# watter_flow_metter_2.net
KiCad netlist of a schematic drawn in EAGLE
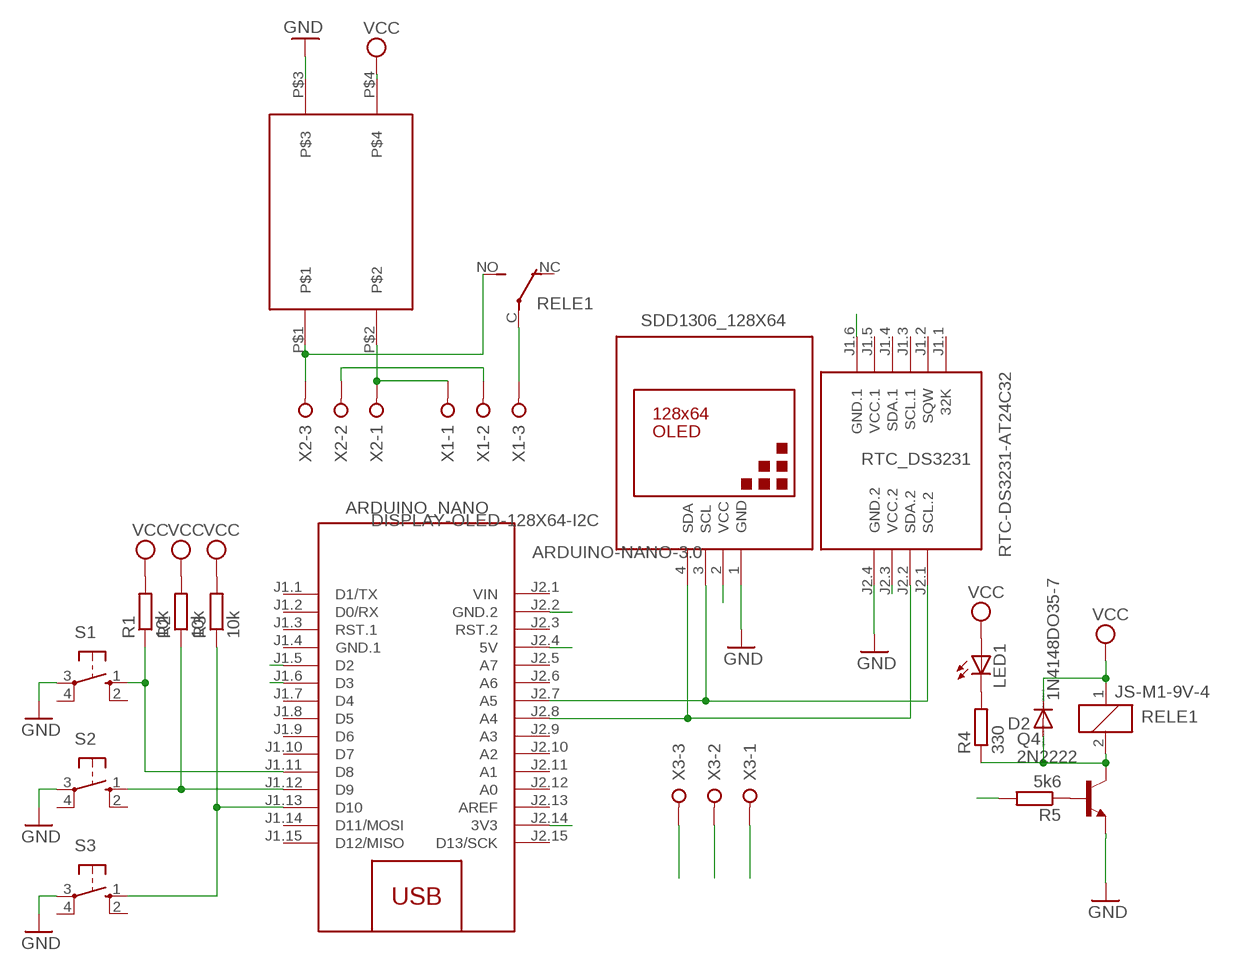
[diagram p0: schematic, sheet 1]

(export (version "E")
  (design (tool "Eeschema 10.0.6"))
  (components
    (comp (ref "ARDUINO_NANO")
      (value "ARDUINO-NANO-3.0")
      (footprint "eagle-import:ARDUINO-NANO-3.0")
      (libsource (lib "eagle-import") (part "ARDUINO-NANO-3.0"))
    )
    (comp (ref "D2")
      (value "1N4148DO35-7")
      (footprint "eagle-import:DO35-7")
      (libsource (lib "eagle-import") (part "1N4148DO35-7"))
    )
    (comp (ref "LED1")
      (value "LED3MM")
      (footprint "eagle-import:LED3MM")
      (libsource (lib "eagle-import") (part "LED3MM"))
    )
    (comp (ref "Q4")
      (value "2N2222")
      (footprint "eagle-import:TO92")
      (libsource (lib "eagle-import") (part "2N5088"))
    )
    (comp (ref "R1")
      (value "10k")
      (footprint "eagle-import:0207_10")
      (libsource (lib "eagle-import") (part "R-EU_0207/10"))
    )
    (comp (ref "R2")
      (value "10k")
      (footprint "eagle-import:0207_10")
      (libsource (lib "eagle-import") (part "R-EU_0207/10"))
    )
    (comp (ref "R3")
      (value "10k")
      (footprint "eagle-import:0207_10")
      (libsource (lib "eagle-import") (part "R-EU_0207/10"))
    )
    (comp (ref "R4")
      (value "330")
      (footprint "eagle-import:0207_10")
      (libsource (lib "eagle-import") (part "R-EU_0207/10"))
    )
    (comp (ref "R5")
      (value "5k6")
      (footprint "eagle-import:0207_10")
      (libsource (lib "eagle-import") (part "R-EU_0207/10"))
    )
    (comp (ref "RELE1")
      (value "JS-M1-9V-4")
      (footprint "eagle-import:JS-M")
      (libsource (lib "eagle-import") (part "JS-M1-9V-4"))
    )
    (comp (ref "RTC_DS3231")
      (value "RTC-DS3231-AT24C32")
      (footprint "eagle-import:RTC-DS3231-AT24C32")
      (libsource (lib "eagle-import") (part "RTC-DS3231-AT24C32"))
    )
    (comp (ref "S1")
      (value "10-XX")
      (footprint "eagle-import:B3F-10XX")
      (fields (field (name "MPN") "B3F-1000"))
      (libsource (lib "eagle-import") (part "10-XX"))
    )
    (comp (ref "S2")
      (value "10-XX")
      (footprint "eagle-import:B3F-10XX")
      (fields (field (name "MPN") "B3F-1000"))
      (libsource (lib "eagle-import") (part "10-XX"))
    )
    (comp (ref "S3")
      (value "10-XX")
      (footprint "eagle-import:B3F-10XX")
      (fields (field (name "MPN") "B3F-1000"))
      (libsource (lib "eagle-import") (part "10-XX"))
    )
    (comp (ref "SDD1306_128X64")
      (value "DISPLAY-OLED-128X64-I2C")
      (footprint "eagle-import:DISPLAY-OLED-128X64-I2C")
      (libsource (lib "eagle-import") (part "DISPLAY-OLED-128X64-I2C"))
    )
    (comp (ref "U$6")
      (value "HLK-PM01")
      (footprint "eagle-import:HLK-PM01")
      (libsource (lib "eagle-import") (part "HLK-PM01"))
    )
    (comp (ref "X1")
      (value "W237-3E")
      (footprint "eagle-import:W237-3E")
      (libsource (lib "eagle-import") (part "W237-3E"))
    )
    (comp (ref "X2")
      (value "W237-3E")
      (footprint "eagle-import:W237-3E")
      (libsource (lib "eagle-import") (part "W237-3E"))
    )
    (comp (ref "X3")
      (value "W237-3E")
      (footprint "eagle-import:W237-3E")
      (libsource (lib "eagle-import") (part "W237-3E"))
    )
  )
  (nets
    (net (code "1") (name "/3.3V") (class "Default")
      (node (ref "ARDUINO_NANO") (pin "J2.14") (pinfunction "3V3_J2.14") (pintype "power_in"))
      (node (ref "RTC_DS3231") (pin "J2.3") (pinfunction "VCC.2_J2.3") (pintype "power_in"))
      (node (ref "SDD1306_128X64") (pin "2") (pinfunction "VCC_2") (pintype "power_in"))
    )
    (net (code "2") (name "/D2") (class "Default")
      (node (ref "ARDUINO_NANO") (pin "J1.5") (pinfunction "D2_J1.5") (pintype "bidirectional"))
      (node (ref "X3") (pin "2") (pinfunction "KL_2") (pintype "passive"))
    )
    (net (code "3") (name "/D3") (class "Default")
      (node (ref "ARDUINO_NANO") (pin "J1.6") (pinfunction "D3_J1.6") (pintype "bidirectional"))
      (node (ref "R5") (pin "2") (pinfunction "2_2") (pintype "passive"))
    )
    (net (code "4") (name "/GND.1") (class "Default")
      (node (ref "ARDUINO_NANO") (pin "J1.4") (pinfunction "GND.1_J1.4") (pintype "power_in"))
    )
    (net (code "5") (name "/VCC.1") (class "Default")
      (node (ref "RTC_DS3231") (pin "J1.5") (pinfunction "VCC.1_J1.5") (pintype "power_in"))
    )
    (net (code "6") (name "/VIN") (class "Default")
      (node (ref "ARDUINO_NANO") (pin "J2.1") (pinfunction "VIN_J2.1") (pintype "power_in"))
    )
    (net (code "7") (name "GND") (class "Default")
      (node (ref "ARDUINO_NANO") (pin "J2.2") (pinfunction "GND.2_J2.2") (pintype "power_in"))
      (node (ref "Q4") (pin "3") (pinfunction "E_3") (pintype "passive"))
      (node (ref "RTC_DS3231") (pin "J2.4") (pinfunction "GND.2_J2.4") (pintype "power_in"))
      (node (ref "S1") (pin "3") (pinfunction "P_3") (pintype "passive"))
      (node (ref "S2") (pin "3") (pinfunction "P_3") (pintype "passive"))
      (node (ref "S3") (pin "3") (pinfunction "P_3") (pintype "passive"))
      (node (ref "SDD1306_128X64") (pin "1") (pinfunction "GND_1") (pintype "power_in"))
      (node (ref "U$6") (pin "P$3") (pinfunction "P$3_P$3") (pintype "bidirectional"))
      (node (ref "X3") (pin "1") (pinfunction "KL_1") (pintype "passive"))
    )
    (net (code "8") (name "Net-(ARDUINO_NANO-A4)") (class "Default")
      (node (ref "ARDUINO_NANO") (pin "J2.8") (pinfunction "A4_J2.8") (pintype "bidirectional"))
      (node (ref "RTC_DS3231") (pin "J2.2") (pinfunction "SDA.2_J2.2") (pintype "bidirectional"))
      (node (ref "SDD1306_128X64") (pin "4") (pinfunction "SDA_4") (pintype "bidirectional"))
    )
    (net (code "9") (name "Net-(ARDUINO_NANO-A5)") (class "Default")
      (node (ref "ARDUINO_NANO") (pin "J2.7") (pinfunction "A5_J2.7") (pintype "bidirectional"))
      (node (ref "RTC_DS3231") (pin "J2.1") (pinfunction "SCL.2_J2.1") (pintype "bidirectional"))
      (node (ref "SDD1306_128X64") (pin "3") (pinfunction "SCL_3") (pintype "bidirectional"))
    )
    (net (code "10") (name "Net-(ARDUINO_NANO-D8)") (class "Default")
      (node (ref "ARDUINO_NANO") (pin "J1.11") (pinfunction "D8_J1.11") (pintype "bidirectional"))
      (node (ref "R1") (pin "1") (pinfunction "1_1") (pintype "passive"))
      (node (ref "S1") (pin "1") (pinfunction "S_1") (pintype "passive"))
    )
    (net (code "11") (name "Net-(ARDUINO_NANO-D9)") (class "Default")
      (node (ref "ARDUINO_NANO") (pin "J1.12") (pinfunction "D9_J1.12") (pintype "bidirectional"))
      (node (ref "R2") (pin "1") (pinfunction "1_1") (pintype "passive"))
      (node (ref "S2") (pin "1") (pinfunction "S_1") (pintype "passive"))
    )
    (net (code "12") (name "Net-(ARDUINO_NANO-D10)") (class "Default")
      (node (ref "ARDUINO_NANO") (pin "J1.13") (pinfunction "D10_J1.13") (pintype "bidirectional"))
      (node (ref "R3") (pin "1") (pinfunction "1_1") (pintype "passive"))
      (node (ref "S3") (pin "1") (pinfunction "S_1") (pintype "passive"))
    )
    (net (code "13") (name "Net-(LED1-C)") (class "Default")
      (node (ref "LED1") (pin "K") (pinfunction "C_K") (pintype "passive"))
      (node (ref "R4") (pin "2") (pinfunction "2_2") (pintype "passive"))
    )
    (net (code "14") (name "Net-(Q4-B)") (class "Default")
      (node (ref "Q4") (pin "2") (pinfunction "B_2") (pintype "passive"))
      (node (ref "R5") (pin "1") (pinfunction "1_1") (pintype "passive"))
    )
    (net (code "15") (name "Net-(Q4-C)") (class "Default")
      (node (ref "D2") (pin "A") (pinfunction "A_A") (pintype "passive"))
      (node (ref "Q4") (pin "1") (pinfunction "C_1") (pintype "passive"))
      (node (ref "R4") (pin "1") (pinfunction "1_1") (pintype "passive"))
      (node (ref "RELE1") (pin "2") (pinfunction "2_2") (pintype "passive"))
    )
    (net (code "16") (name "Net-(RELE1B-P)") (class "Default")
      (node (ref "RELE1") (pin "C") (pinfunction "P_C") (pintype "passive"))
      (node (ref "X1") (pin "3") (pinfunction "KL_3") (pintype "passive"))
    )
    (net (code "17") (name "Net-(RELE1B-S)") (class "Default")
      (node (ref "RELE1") (pin "NO") (pinfunction "S_NO") (pintype "passive"))
      (node (ref "U$6") (pin "P$1") (pinfunction "P$1_P$1") (pintype "bidirectional"))
      (node (ref "X2") (pin "3") (pinfunction "KL_3") (pintype "passive"))
    )
    (net (code "18") (name "Net-(X1A-KL)") (class "Default")
      (node (ref "U$6") (pin "P$2") (pinfunction "P$2_P$2") (pintype "bidirectional"))
      (node (ref "X1") (pin "1") (pinfunction "KL_1") (pintype "passive"))
      (node (ref "X2") (pin "1") (pinfunction "KL_1") (pintype "passive"))
    )
    (net (code "19") (name "Net-(X1B-KL)") (class "Default")
      (node (ref "X1") (pin "2") (pinfunction "KL_2") (pintype "passive"))
      (node (ref "X2") (pin "2") (pinfunction "KL_2") (pintype "passive"))
    )
    (net (code "20") (name "VCC") (class "Default")
      (node (ref "ARDUINO_NANO") (pin "J2.4") (pinfunction "5V_J2.4") (pintype "power_in"))
      (node (ref "D2") (pin "C") (pinfunction "C_C") (pintype "passive"))
      (node (ref "LED1") (pin "A") (pinfunction "A_A") (pintype "passive"))
      (node (ref "R1") (pin "2") (pinfunction "2_2") (pintype "passive"))
      (node (ref "R2") (pin "2") (pinfunction "2_2") (pintype "passive"))
      (node (ref "R3") (pin "2") (pinfunction "2_2") (pintype "passive"))
      (node (ref "RELE1") (pin "1") (pinfunction "1_1") (pintype "passive"))
      (node (ref "U$6") (pin "P$4") (pinfunction "P$4_P$4") (pintype "bidirectional"))
      (node (ref "X3") (pin "3") (pinfunction "KL_3") (pintype "passive"))
    )
    (net (code "21") (name "unconnected-(ARDUINO_NANO-A0-PadJ2.12)") (class "Default")
      (node (ref "ARDUINO_NANO") (pin "J2.12") (pinfunction "A0_J2.12") (pintype "bidirectional"))
    )
    (net (code "22") (name "unconnected-(ARDUINO_NANO-A1-PadJ2.11)") (class "Default")
      (node (ref "ARDUINO_NANO") (pin "J2.11") (pinfunction "A1_J2.11") (pintype "bidirectional"))
    )
    (net (code "23") (name "unconnected-(ARDUINO_NANO-A2-PadJ2.10)") (class "Default")
      (node (ref "ARDUINO_NANO") (pin "J2.10") (pinfunction "A2_J2.10") (pintype "bidirectional"))
    )
    (net (code "24") (name "unconnected-(ARDUINO_NANO-A3-PadJ2.9)") (class "Default")
      (node (ref "ARDUINO_NANO") (pin "J2.9") (pinfunction "A3_J2.9") (pintype "bidirectional"))
    )
    (net (code "25") (name "unconnected-(ARDUINO_NANO-A6-PadJ2.6)") (class "Default")
      (node (ref "ARDUINO_NANO") (pin "J2.6") (pinfunction "A6_J2.6") (pintype "bidirectional"))
    )
    (net (code "26") (name "unconnected-(ARDUINO_NANO-A7-PadJ2.5)") (class "Default")
      (node (ref "ARDUINO_NANO") (pin "J2.5") (pinfunction "A7_J2.5") (pintype "bidirectional"))
    )
    (net (code "27") (name "unconnected-(ARDUINO_NANO-AREF-PadJ2.13)") (class "Default")
      (node (ref "ARDUINO_NANO") (pin "J2.13") (pinfunction "AREF_J2.13") (pintype "bidirectional"))
    )
    (net (code "28") (name "unconnected-(ARDUINO_NANO-D0{slash}RX-PadJ1.2)") (class "Default")
      (node (ref "ARDUINO_NANO") (pin "J1.2") (pinfunction "D0/RX_J1.2") (pintype "bidirectional"))
    )
    (net (code "29") (name "unconnected-(ARDUINO_NANO-D1{slash}TX-PadJ1.1)") (class "Default")
      (node (ref "ARDUINO_NANO") (pin "J1.1") (pinfunction "D1/TX_J1.1") (pintype "bidirectional"))
    )
    (net (code "30") (name "unconnected-(ARDUINO_NANO-D4-PadJ1.7)") (class "Default")
      (node (ref "ARDUINO_NANO") (pin "J1.7") (pinfunction "D4_J1.7") (pintype "bidirectional"))
    )
    (net (code "31") (name "unconnected-(ARDUINO_NANO-D5-PadJ1.8)") (class "Default")
      (node (ref "ARDUINO_NANO") (pin "J1.8") (pinfunction "D5_J1.8") (pintype "bidirectional"))
    )
    (net (code "32") (name "unconnected-(ARDUINO_NANO-D6-PadJ1.9)") (class "Default")
      (node (ref "ARDUINO_NANO") (pin "J1.9") (pinfunction "D6_J1.9") (pintype "bidirectional"))
    )
    (net (code "33") (name "unconnected-(ARDUINO_NANO-D7-PadJ1.10)") (class "Default")
      (node (ref "ARDUINO_NANO") (pin "J1.10") (pinfunction "D7_J1.10") (pintype "bidirectional"))
    )
    (net (code "34") (name "unconnected-(ARDUINO_NANO-D11{slash}MOSI-PadJ1.14)") (class "Default")
      (node (ref "ARDUINO_NANO") (pin "J1.14") (pinfunction "D11/MOSI_J1.14") (pintype "bidirectional"))
    )
    (net (code "35") (name "unconnected-(ARDUINO_NANO-D12{slash}MISO-PadJ1.15)") (class "Default")
      (node (ref "ARDUINO_NANO") (pin "J1.15") (pinfunction "D12/MISO_J1.15") (pintype "bidirectional"))
    )
    (net (code "36") (name "unconnected-(ARDUINO_NANO-D13{slash}SCK-PadJ2.15)") (class "Default")
      (node (ref "ARDUINO_NANO") (pin "J2.15") (pinfunction "D13/SCK_J2.15") (pintype "bidirectional"))
    )
    (net (code "37") (name "unconnected-(ARDUINO_NANO-RST.1-PadJ1.3)") (class "Default")
      (node (ref "ARDUINO_NANO") (pin "J1.3") (pinfunction "RST.1_J1.3") (pintype "bidirectional"))
    )
    (net (code "38") (name "unconnected-(ARDUINO_NANO-RST.2-PadJ2.3)") (class "Default")
      (node (ref "ARDUINO_NANO") (pin "J2.3") (pinfunction "RST.2_J2.3") (pintype "bidirectional"))
    )
    (net (code "39") (name "unconnected-(RELE1B-O-PadNC)") (class "Default")
      (node (ref "RELE1") (pin "NC") (pinfunction "O_NC") (pintype "passive"))
    )
    (net (code "40") (name "unconnected-(RTC_DS3231-32K-PadJ1.1)") (class "Default")
      (node (ref "RTC_DS3231") (pin "J1.1") (pinfunction "32K_J1.1") (pintype "bidirectional"))
    )
    (net (code "41") (name "unconnected-(RTC_DS3231-GND.1-PadJ1.6)") (class "Default")
      (node (ref "RTC_DS3231") (pin "J1.6") (pinfunction "GND.1_J1.6") (pintype "power_in"))
    )
    (net (code "42") (name "unconnected-(RTC_DS3231-SCL.1-PadJ1.3)") (class "Default")
      (node (ref "RTC_DS3231") (pin "J1.3") (pinfunction "SCL.1_J1.3") (pintype "bidirectional"))
    )
    (net (code "43") (name "unconnected-(RTC_DS3231-SDA.1-PadJ1.4)") (class "Default")
      (node (ref "RTC_DS3231") (pin "J1.4") (pinfunction "SDA.1_J1.4") (pintype "bidirectional"))
    )
    (net (code "44") (name "unconnected-(RTC_DS3231-SQW-PadJ1.2)") (class "Default")
      (node (ref "RTC_DS3231") (pin "J1.2") (pinfunction "SQW_J1.2") (pintype "bidirectional"))
    )
    (net (code "45") (name "unconnected-(S1-P1-Pad4)") (class "Default")
      (node (ref "S1") (pin "4") (pinfunction "P1_4") (pintype "passive"))
    )
    (net (code "46") (name "unconnected-(S1-S1-Pad2)") (class "Default")
      (node (ref "S1") (pin "2") (pinfunction "S1_2") (pintype "passive"))
    )
    (net (code "47") (name "unconnected-(S2-P1-Pad4)") (class "Default")
      (node (ref "S2") (pin "4") (pinfunction "P1_4") (pintype "passive"))
    )
    (net (code "48") (name "unconnected-(S2-S1-Pad2)") (class "Default")
      (node (ref "S2") (pin "2") (pinfunction "S1_2") (pintype "passive"))
    )
    (net (code "49") (name "unconnected-(S3-P1-Pad4)") (class "Default")
      (node (ref "S3") (pin "4") (pinfunction "P1_4") (pintype "passive"))
    )
    (net (code "50") (name "unconnected-(S3-S1-Pad2)") (class "Default")
      (node (ref "S3") (pin "2") (pinfunction "S1_2") (pintype "passive"))
    )
  )
)
